# Servo_Power_Board.net
KiCad netlist of a schematic drawn in EasyEDA Pro
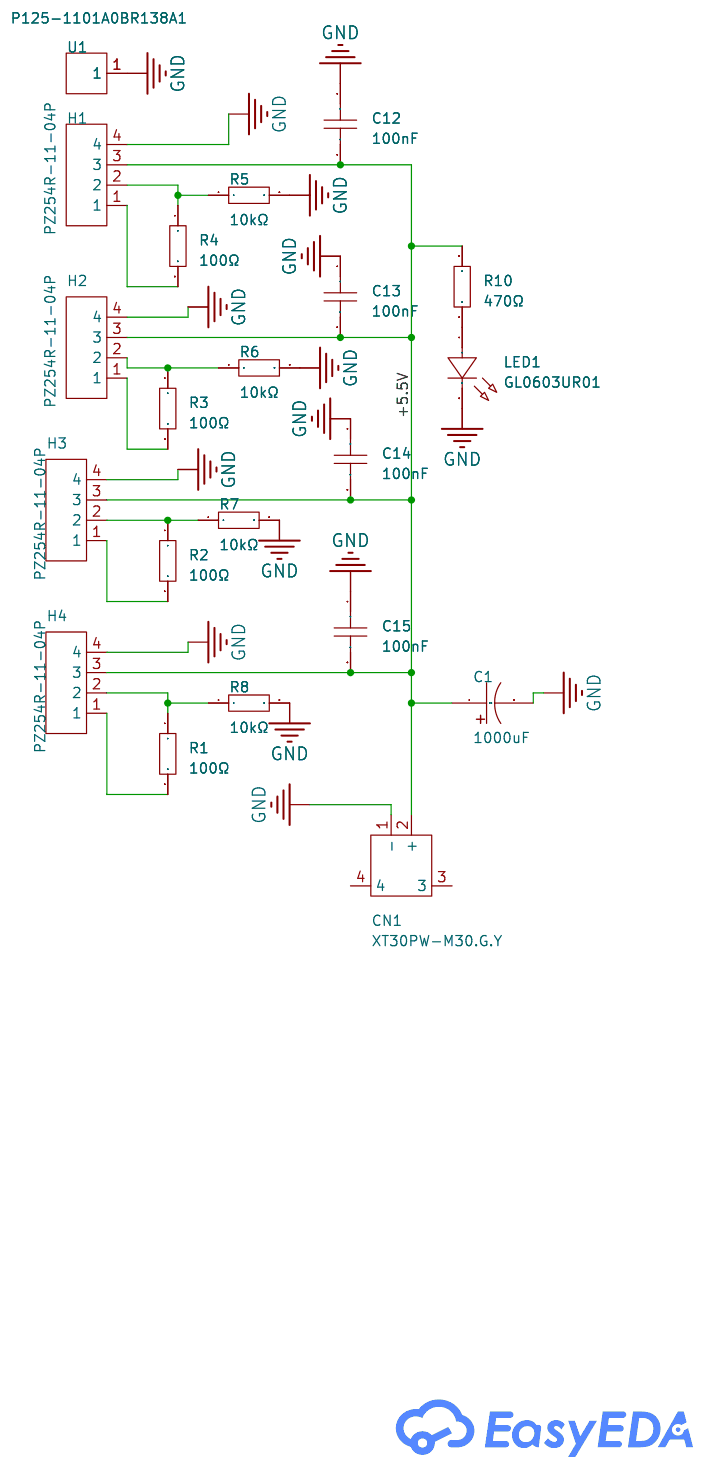
[diagram p0: schematic sheet]

(export (version "E")
  (design (tool "Eeschema 10.0.6"))
  (components
    (comp (ref "C1")
      (value "1000uF")
      (footprint "easyedapro:CAP-SMD_BD10.0-L10.3-W10.3-LS11.0-R-RD")
      (fields (field (name "Manufacturer Part") "VZH102M1ATR-1010") (field (name "Manufacturer") "Lelon(立隆)"))
      (libsource (lib "easyedapro") (part "VZH102M1ATR-1010"))
    )
    (comp (ref "C12")
      (value "100nF")
      (footprint "easyedapro:C0603")
      (libsource (lib "easyedapro") (part "CAP"))
    )
    (comp (ref "C13")
      (value "100nF")
      (footprint "easyedapro:C0603")
      (libsource (lib "easyedapro") (part "CAP"))
    )
    (comp (ref "C14")
      (value "100nF")
      (footprint "easyedapro:C0603")
      (libsource (lib "easyedapro") (part "CAP"))
    )
    (comp (ref "C15")
      (value "100nF")
      (footprint "easyedapro:C0603")
      (libsource (lib "easyedapro") (part "CAP"))
    )
    (comp (ref "CN1")
      (value "XT30PW-M30.G.Y")
      (footprint "easyedapro:CONN-TH_XT30PW-M")
      (fields (field (name "Manufacturer") "AMASS(艾迈斯)"))
      (libsource (lib "easyedapro") (part "XT30PW-M"))
    )
    (comp (ref "H1")
      (value "PZ254R-11-04P")
      (footprint "easyedapro:HDR-TH_4P-P2.54-H-M-W10.4")
      (fields (field (name "Manufacturer") "XFCN(兴飞)"))
      (libsource (lib "easyedapro") (part "PZ254R-11-04P"))
    )
    (comp (ref "H2")
      (value "PZ254R-11-04P")
      (footprint "easyedapro:HDR-TH_4P-P2.54-H-M-W10.4")
      (fields (field (name "Manufacturer") "XFCN(兴飞)"))
      (libsource (lib "easyedapro") (part "PZ254R-11-04P"))
    )
    (comp (ref "H3")
      (value "PZ254R-11-04P")
      (footprint "easyedapro:HDR-TH_4P-P2.54-H-M-W10.4")
      (fields (field (name "Manufacturer") "XFCN(兴飞)"))
      (libsource (lib "easyedapro") (part "PZ254R-11-04P"))
    )
    (comp (ref "H4")
      (value "PZ254R-11-04P")
      (footprint "easyedapro:HDR-TH_4P-P2.54-H-M-W10.4")
      (fields (field (name "Manufacturer") "XFCN(兴飞)"))
      (libsource (lib "easyedapro") (part "PZ254R-11-04P"))
    )
    (comp (ref "LED1")
      (value "GL0603UR01")
      (footprint "easyedapro:LED0603-FD")
      (fields (field (name "Manufacturer") "Guiguang light(桂光光电)"))
      (libsource (lib "easyedapro") (part "GL0603UR01"))
    )
    (comp (ref "R1")
      (value "100Ω")
      (footprint "easyedapro:R0603")
      (libsource (lib "easyedapro") (part "Res"))
    )
    (comp (ref "R2")
      (value "100Ω")
      (footprint "easyedapro:R0603")
      (libsource (lib "easyedapro") (part "Res"))
    )
    (comp (ref "R3")
      (value "100Ω")
      (footprint "easyedapro:R0603")
      (libsource (lib "easyedapro") (part "Res"))
    )
    (comp (ref "R4")
      (value "100Ω")
      (footprint "easyedapro:R0603")
      (libsource (lib "easyedapro") (part "Res"))
    )
    (comp (ref "R5")
      (value "10kΩ")
      (footprint "easyedapro:R0603")
      (libsource (lib "easyedapro") (part "Res"))
    )
    (comp (ref "R6")
      (value "10kΩ")
      (footprint "easyedapro:R0603")
      (libsource (lib "easyedapro") (part "Res"))
    )
    (comp (ref "R7")
      (value "10kΩ")
      (footprint "easyedapro:R0603")
      (libsource (lib "easyedapro") (part "Res"))
    )
    (comp (ref "R8")
      (value "10kΩ")
      (footprint "easyedapro:R0603")
      (libsource (lib "easyedapro") (part "Res"))
    )
    (comp (ref "R10")
      (value "470Ω")
      (footprint "easyedapro:R0603")
      (libsource (lib "easyedapro") (part "Res"))
    )
    (comp (ref "U1")
      (value "P125-1101A0BR138A1")
      (footprint "easyedapro:HDR-TH_1P-P2.54-H-M-W9.7-N")
      (fields (field (name "Manufacturer") "Yxcon(宇熙精密)"))
      (libsource (lib "easyedapro") (part "P125-1101A0BR138A1"))
    )
  )
  (nets
    (net (code "1") (name "/+5.5V") (class "Default")
      (node (ref "C1") (pin "1") (pinfunction "1_1") (pintype "unspecified"))
      (node (ref "C12") (pin "2") (pinfunction "2_2") (pintype "input"))
      (node (ref "C13") (pin "2") (pinfunction "2_2") (pintype "input"))
      (node (ref "C14") (pin "2") (pinfunction "2_2") (pintype "input"))
      (node (ref "C15") (pin "2") (pinfunction "2_2") (pintype "input"))
      (node (ref "CN1") (pin "2") (pinfunction "+_2") (pintype "unspecified"))
      (node (ref "H1") (pin "3") (pinfunction "3_3") (pintype "unspecified"))
      (node (ref "H2") (pin "3") (pinfunction "3_3") (pintype "unspecified"))
      (node (ref "H3") (pin "3") (pinfunction "3_3") (pintype "unspecified"))
      (node (ref "H4") (pin "3") (pinfunction "3_3") (pintype "unspecified"))
      (node (ref "R10") (pin "2") (pinfunction "2_2") (pintype "input"))
    )
    (net (code "2") (name "GND") (class "Default")
      (node (ref "C1") (pin "2") (pinfunction "2_2") (pintype "unspecified"))
      (node (ref "C12") (pin "1") (pinfunction "1_1") (pintype "input"))
      (node (ref "C13") (pin "1") (pinfunction "1_1") (pintype "input"))
      (node (ref "C14") (pin "1") (pinfunction "1_1") (pintype "input"))
      (node (ref "C15") (pin "1") (pinfunction "1_1") (pintype "input"))
      (node (ref "CN1") (pin "1") (pinfunction "-_1") (pintype "unspecified"))
      (node (ref "H1") (pin "4") (pinfunction "4_4") (pintype "unspecified"))
      (node (ref "H2") (pin "4") (pinfunction "4_4") (pintype "unspecified"))
      (node (ref "H3") (pin "4") (pinfunction "4_4") (pintype "unspecified"))
      (node (ref "H4") (pin "4") (pinfunction "4_4") (pintype "unspecified"))
      (node (ref "LED1") (pin "2") (pinfunction "C_2") (pintype "unspecified"))
      (node (ref "R5") (pin "2") (pinfunction "2_2") (pintype "input"))
      (node (ref "R6") (pin "2") (pinfunction "2_2") (pintype "input"))
      (node (ref "R7") (pin "2") (pinfunction "2_2") (pintype "input"))
      (node (ref "R8") (pin "2") (pinfunction "2_2") (pintype "input"))
      (node (ref "U1") (pin "1") (pinfunction "1_1") (pintype "unspecified"))
    )
    (net (code "3") (name "Net-(H1-Pad1)") (class "Default")
      (node (ref "H1") (pin "1") (pinfunction "1_1") (pintype "unspecified"))
      (node (ref "R4") (pin "2") (pinfunction "2_2") (pintype "input"))
    )
    (net (code "4") (name "Net-(H1-Pad2)") (class "Default")
      (node (ref "H1") (pin "2") (pinfunction "2_2") (pintype "unspecified"))
      (node (ref "R4") (pin "1") (pinfunction "1_1") (pintype "input"))
      (node (ref "R5") (pin "1") (pinfunction "1_1") (pintype "input"))
    )
    (net (code "5") (name "Net-(H2-Pad1)") (class "Default")
      (node (ref "H2") (pin "1") (pinfunction "1_1") (pintype "unspecified"))
      (node (ref "R3") (pin "2") (pinfunction "2_2") (pintype "input"))
    )
    (net (code "6") (name "Net-(H2-Pad2)") (class "Default")
      (node (ref "H2") (pin "2") (pinfunction "2_2") (pintype "unspecified"))
      (node (ref "R3") (pin "1") (pinfunction "1_1") (pintype "input"))
      (node (ref "R6") (pin "1") (pinfunction "1_1") (pintype "input"))
    )
    (net (code "7") (name "Net-(H3-Pad1)") (class "Default")
      (node (ref "H3") (pin "1") (pinfunction "1_1") (pintype "unspecified"))
      (node (ref "R2") (pin "2") (pinfunction "2_2") (pintype "input"))
    )
    (net (code "8") (name "Net-(H3-Pad2)") (class "Default")
      (node (ref "H3") (pin "2") (pinfunction "2_2") (pintype "unspecified"))
      (node (ref "R2") (pin "1") (pinfunction "1_1") (pintype "input"))
      (node (ref "R7") (pin "1") (pinfunction "1_1") (pintype "input"))
    )
    (net (code "9") (name "Net-(H4-Pad1)") (class "Default")
      (node (ref "H4") (pin "1") (pinfunction "1_1") (pintype "unspecified"))
      (node (ref "R1") (pin "2") (pinfunction "2_2") (pintype "input"))
    )
    (net (code "10") (name "Net-(H4-Pad2)") (class "Default")
      (node (ref "H4") (pin "2") (pinfunction "2_2") (pintype "unspecified"))
      (node (ref "R1") (pin "1") (pinfunction "1_1") (pintype "input"))
      (node (ref "R8") (pin "1") (pinfunction "1_1") (pintype "input"))
    )
    (net (code "11") (name "Net-(LED1-A)") (class "Default")
      (node (ref "LED1") (pin "1") (pinfunction "A_1") (pintype "unspecified"))
      (node (ref "R10") (pin "1") (pinfunction "1_1") (pintype "input"))
    )
    (net (code "12") (name "unconnected-(CN1-Pad3)") (class "Default")
      (node (ref "CN1") (pin "3") (pinfunction "3_3") (pintype "unspecified"))
    )
    (net (code "13") (name "unconnected-(CN1-Pad4)") (class "Default")
      (node (ref "CN1") (pin "4") (pinfunction "4_4") (pintype "unspecified"))
    )
  )
)
